# MC21R01_Inverter_2.net
KiCad netlist of a schematic drawn in Altium Designer
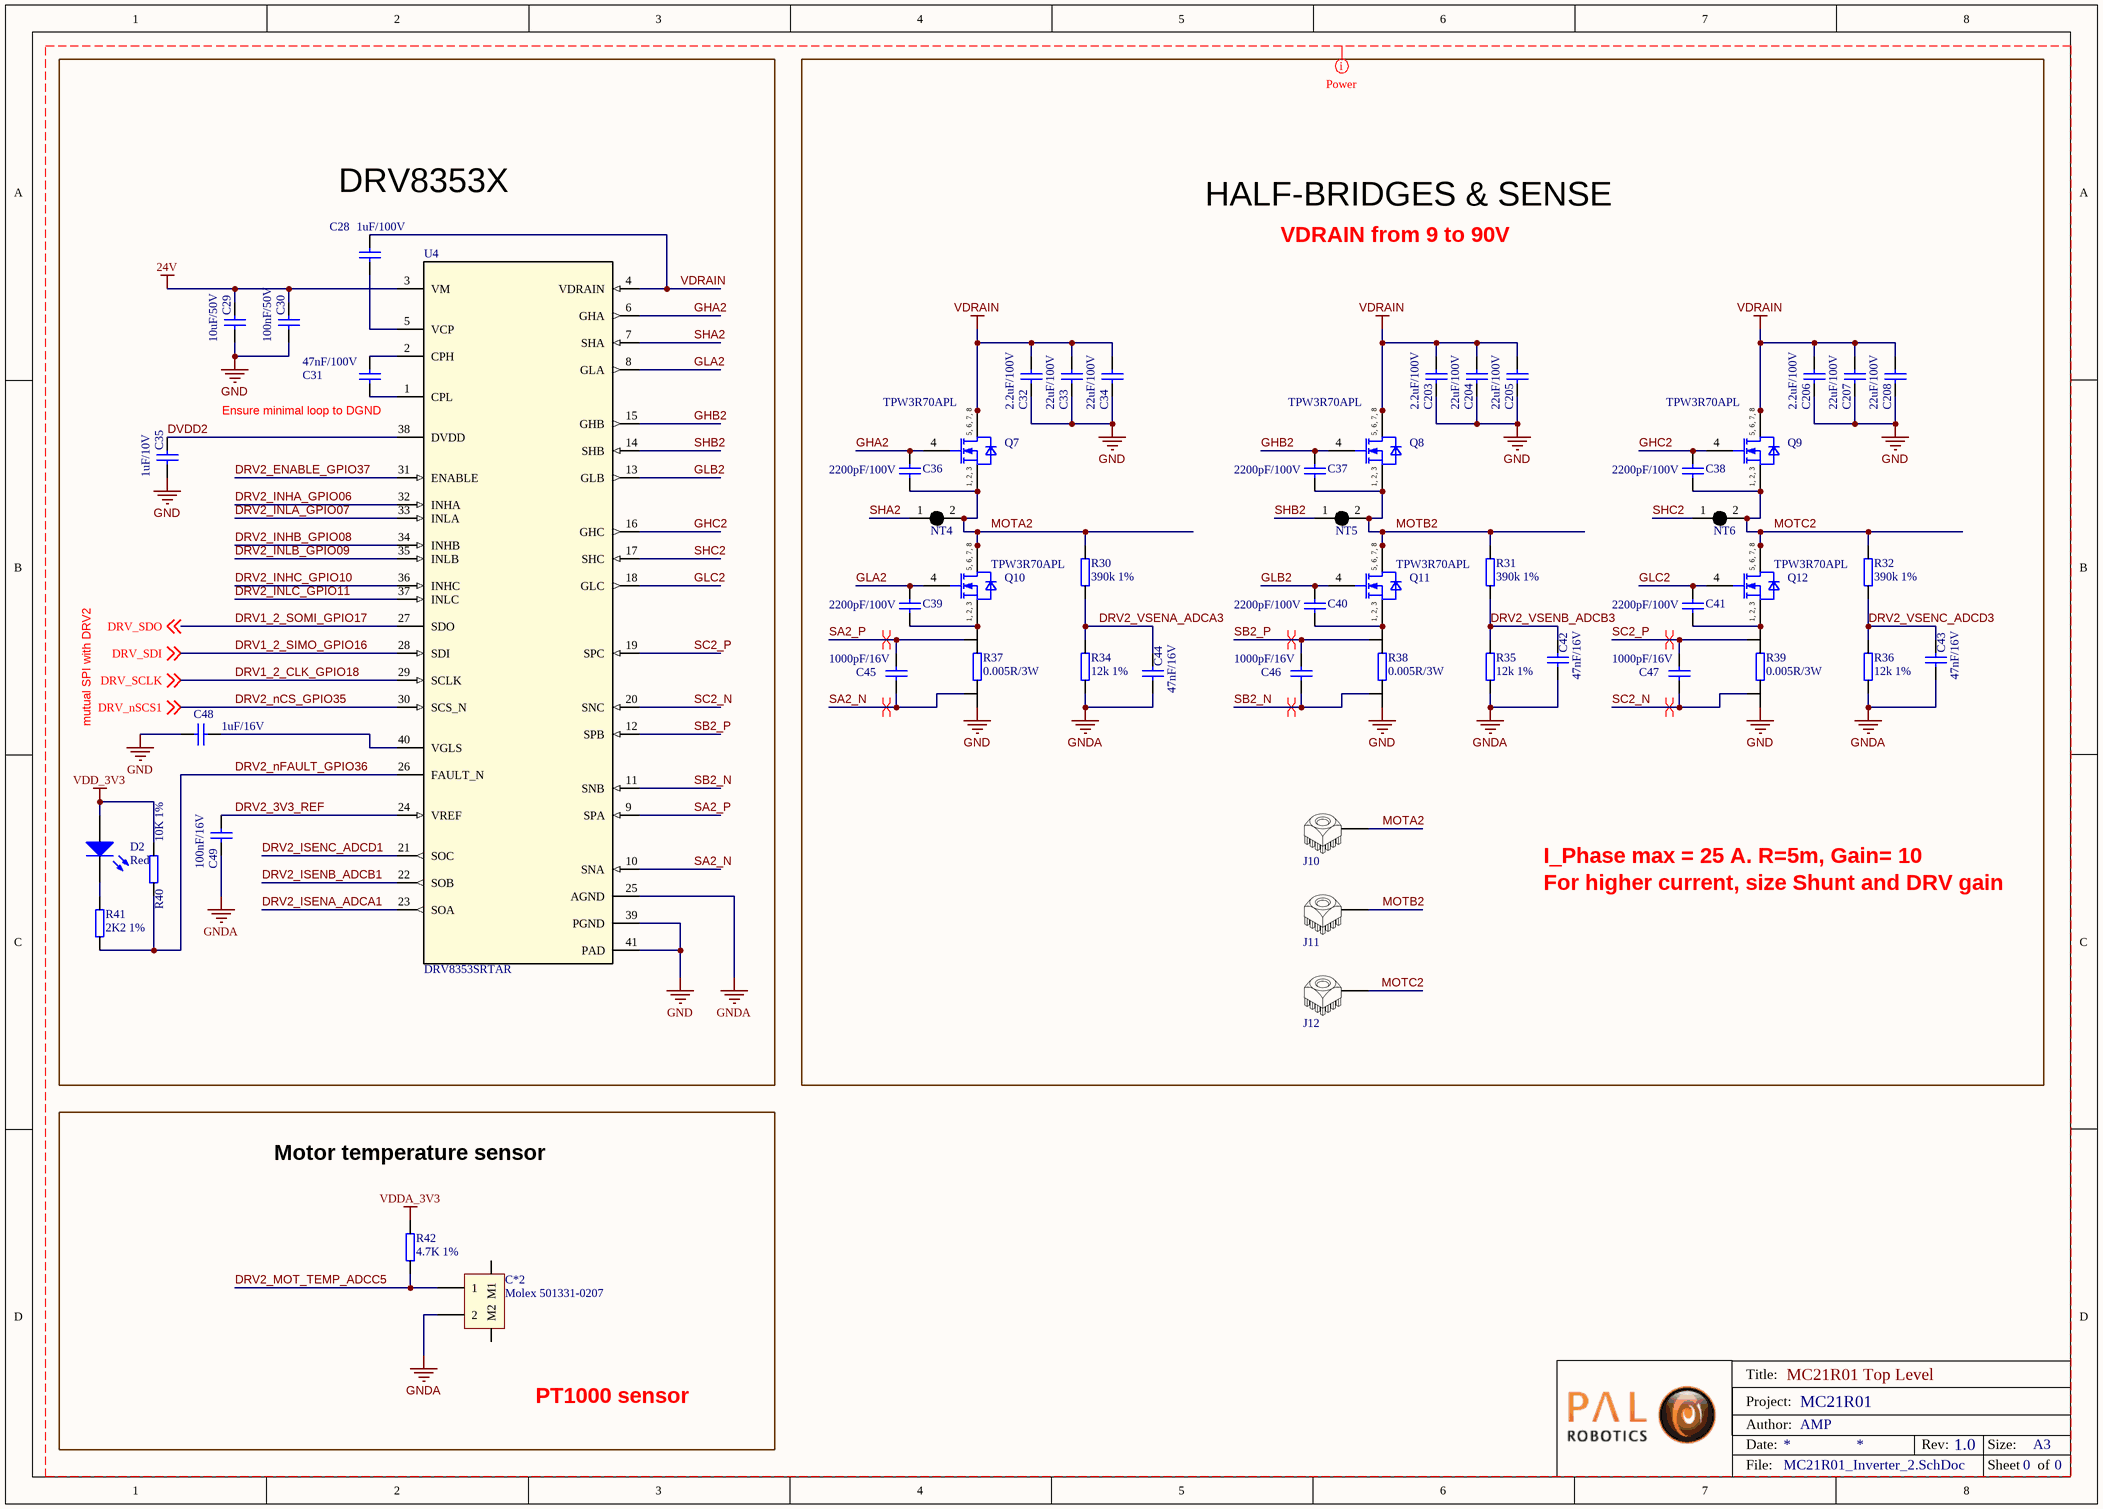
[diagram p0: MC21R01_Inverter_2.SchDoc]

(export (version "E")
  (design (tool "Eeschema 10.0.6"))
  (components
    (comp (ref "C*2")
      (value "Molex 501331-0207")
      (footprint "Molex 501331-0207")
      (description "PicoClasp 02 pin vertical")
      (libsource (lib "PAL_Molex") (part "Molex 501331-0207"))
    )
    (comp (ref "C28")
      (value "1uF/100V")
      (footprint "PAL_Capacitors:0805 SMD capacitor")
      (description "1 uF 100 V 0805  ±10% Tolerance X7R Multilayer Ceramic Chip Capacitor")
      (fields (field (name "Comment") "1uF/100V 0805 10% X7R"))
      (libsource (lib "PAL_Capacitors") (part "1uF/100V 0805 10% X7R"))
    )
    (comp (ref "C29")
      (value "10uF/50V")
      (footprint "PAL_Capacitors:1206 SMD Capacitor")
      (description "10 uF 50 V 1206 ±20% Tolerance X5R Multilayer Ceramic Chip Capacitor")
      (fields (field (name "Comment") "10uf/50V 1206 20% X5R"))
      (libsource (lib "PAL_Capacitors") (part "10uF/50V 1206 20% X5R"))
    )
    (comp (ref "C30")
      (value "100nF/50V")
      (footprint "PAL_Capacitors:0603 SMD capacitor")
      (description "100 nF 50 V 0603  ±10% Tolerance X7R Multilayer Ceramic Chip Capacitor")
      (fields (field (name "Comment") "100nF/50V 0603 10% X7R"))
      (libsource (lib "PAL_Capacitors") (part "100nF/50V 0603 10% X7R"))
    )
    (comp (ref "C31")
      (value "47nF/100V")
      (footprint "PAL_Capacitors:0603 SMD capacitor")
      (description "47 nF 100 V 0603 ±10% Tolerance X7R Multilayer Ceramic Chip Capacitor")
      (fields (field (name "Comment") "47nF/100V 0603 10% X7R"))
      (libsource (lib "PAL_Capacitors") (part "47nF/100V 0603 10% X7R_1"))
    )
    (comp (ref "C32")
      (value "2.2uF/100V")
      (footprint "1210 SMD capacitor h=2mm")
      (description "2.2 uF 100 V 1210  ±10% Tolerance X7R Multilayer Ceramic Chip Capacitor")
      (fields (field (name "Comment") "2.2uF/100V 1210 10% X7R"))
      (libsource (lib "PAL_Capacitors") (part "2.2uF/100V 1210 10% X7R"))
    )
    (comp (ref "C33")
      (value "22uF/100V")
      (footprint "PAL_Capacitors:2220 SMD Capacitor H=5MM")
      (description "22 uF 100 V 2220 ±20% Tolerance X7S Multilayer Ceramic Chip Capacitor")
      (fields (field (name "Comment") "22uF/100V 2220 20% X7S"))
      (libsource (lib "PAL_Capacitors") (part "22uF/100V 2220 20% X7S"))
    )
    (comp (ref "C34")
      (value "22uF/100V")
      (footprint "PAL_Capacitors:2220 SMD Capacitor H=5MM")
      (description "22 uF 100 V 2220 ±20% Tolerance X7S Multilayer Ceramic Chip Capacitor")
      (fields (field (name "Comment") "22uF/100V 2220 20% X7S"))
      (libsource (lib "PAL_Capacitors") (part "22uF/100V 2220 20% X7S"))
    )
    (comp (ref "C35")
      (value "1uF/10V")
      (footprint "PAL_Capacitors:0603 SMD capacitor")
      (description "1uF/10V 0603 10% Tolerance X7R Multilayer Ceramic Chip Capacitor")
      (fields (field (name "Comment") "1uF/10V 0603 10% X7R"))
      (libsource (lib "PAL_Capacitors") (part "1uF/10V 0603 10% X7R"))
    )
    (comp (ref "C36")
      (value "2200pF/100V")
      (footprint "PAL_Capacitors:0402 SMD Capacitor")
      (description "2200pF/100V 0402 10% Tolerance X7S Multilayer Ceramic Chip Capacitor")
      (fields (field (name "Comment") "2200pF/100V 0402 10% X7S"))
      (libsource (lib "PAL_Capacitors") (part "2200pF/100V 0402 10% X7S"))
    )
    (comp (ref "C37")
      (value "2200pF/100V")
      (footprint "PAL_Capacitors:0402 SMD Capacitor")
      (description "2200pF/100V 0402 10% Tolerance X7S Multilayer Ceramic Chip Capacitor")
      (fields (field (name "Comment") "2200pF/100V 0402 10% X7S"))
      (libsource (lib "PAL_Capacitors") (part "2200pF/100V 0402 10% X7S"))
    )
    (comp (ref "C38")
      (value "2200pF/100V")
      (footprint "PAL_Capacitors:0402 SMD Capacitor")
      (description "2200pF/100V 0402 10% Tolerance X7S Multilayer Ceramic Chip Capacitor")
      (fields (field (name "Comment") "2200pF/100V 0402 10% X7S"))
      (libsource (lib "PAL_Capacitors") (part "2200pF/100V 0402 10% X7S"))
    )
    (comp (ref "C39")
      (value "2200pF/100V")
      (footprint "PAL_Capacitors:0402 SMD Capacitor")
      (description "2200pF/100V 0402 10% Tolerance X7S Multilayer Ceramic Chip Capacitor")
      (fields (field (name "Comment") "2200pF/100V 0402 10% X7S"))
      (libsource (lib "PAL_Capacitors") (part "2200pF/100V 0402 10% X7S"))
    )
    (comp (ref "C40")
      (value "2200pF/100V")
      (footprint "PAL_Capacitors:0402 SMD Capacitor")
      (description "2200pF/100V 0402 10% Tolerance X7S Multilayer Ceramic Chip Capacitor")
      (fields (field (name "Comment") "2200pF/100V 0402 10% X7S"))
      (libsource (lib "PAL_Capacitors") (part "2200pF/100V 0402 10% X7S"))
    )
    (comp (ref "C41")
      (value "2200pF/100V")
      (footprint "PAL_Capacitors:0402 SMD Capacitor")
      (description "2200pF/100V 0402 10% Tolerance X7S Multilayer Ceramic Chip Capacitor")
      (fields (field (name "Comment") "2200pF/100V 0402 10% X7S"))
      (libsource (lib "PAL_Capacitors") (part "2200pF/100V 0402 10% X7S"))
    )
    (comp (ref "C42")
      (value "47nF/16V")
      (footprint "PAL_Capacitors:0402 SMD Capacitor")
      (description "47nF/16V 0402 10% Tolerance X7R Multilayer Ceramic Chip Capacitor")
      (fields (field (name "Comment") "47nF/16V 0402 10% X7R"))
      (libsource (lib "PAL_Capacitors") (part "47nF/16V 0402 10% X7R"))
    )
    (comp (ref "C43")
      (value "47nF/16V")
      (footprint "PAL_Capacitors:0402 SMD Capacitor")
      (description "47nF/16V 0402 10% Tolerance X7R Multilayer Ceramic Chip Capacitor")
      (fields (field (name "Comment") "47nF/16V 0402 10% X7R"))
      (libsource (lib "PAL_Capacitors") (part "47nF/16V 0402 10% X7R"))
    )
    (comp (ref "C44")
      (value "47nF/16V")
      (footprint "PAL_Capacitors:0402 SMD Capacitor")
      (description "47nF/16V 0402 10% Tolerance X7R Multilayer Ceramic Chip Capacitor")
      (fields (field (name "Comment") "47nF/16V 0402 10% X7R"))
      (libsource (lib "PAL_Capacitors") (part "47nF/16V 0402 10% X7R"))
    )
    (comp (ref "C45")
      (value "1000pF/16V")
      (footprint "PAL_Capacitors:0402 SMD Capacitor")
      (description "1000pF/16V 0402 10% Tolerance X7R Multilayer Ceramic Chip Capacitor")
      (fields (field (name "Comment") "1000pF/16V 0402 10% X7R"))
      (libsource (lib "PAL_Capacitors") (part "1000pF/16V 0402 10% X7R_1"))
    )
    (comp (ref "C46")
      (value "1000pF/16V")
      (footprint "PAL_Capacitors:0402 SMD Capacitor")
      (description "1000pF/16V 0402 10% Tolerance X7R Multilayer Ceramic Chip Capacitor")
      (fields (field (name "Comment") "1000pF/16V 0402 10% X7R"))
      (libsource (lib "PAL_Capacitors") (part "1000pF/16V 0402 10% X7R_1"))
    )
    (comp (ref "C47")
      (value "1000pF/16V")
      (footprint "PAL_Capacitors:0402 SMD Capacitor")
      (description "1000pF/16V 0402 10% Tolerance X7R Multilayer Ceramic Chip Capacitor")
      (fields (field (name "Comment") "1000pF/16V 0402 10% X7R"))
      (libsource (lib "PAL_Capacitors") (part "1000pF/16V 0402 10% X7R_1"))
    )
    (comp (ref "C48")
      (value "1uF/16V")
      (footprint "PAL_Capacitors:0603 SMD capacitor")
      (description "1uF/16V 0603 10% Tolerance X7R Multilayer Ceramic Chip Capacitor")
      (fields (field (name "Comment") "1uF/16V 0603 10% X7R"))
      (libsource (lib "PAL_Capacitors") (part "1uF/16V 0603 10% X7R"))
    )
    (comp (ref "C49")
      (value "100nF/16V")
      (footprint "PAL_Capacitors:0402 SMD Capacitor")
      (description "100nF/16V 0402 10% Tolerance X7R Multilayer Ceramic Chip Capacitor")
      (fields (field (name "Comment") "100nF/16V 0402 10% X7R"))
      (libsource (lib "PAL_Capacitors") (part "100nF/16V 0402 10% X7R"))
    )
    (comp (ref "C203")
      (value "2.2uF/100V")
      (footprint "1210 SMD capacitor h=2mm")
      (description "2.2 uF 100 V 1210  ±10% Tolerance X7R Multilayer Ceramic Chip Capacitor")
      (fields (field (name "Comment") "2.2uF/100V 1210 10% X7R"))
      (libsource (lib "PAL_Capacitors") (part "2.2uF/100V 1210 10% X7R"))
    )
    (comp (ref "C204")
      (value "22uF/100V")
      (footprint "PAL_Capacitors:2220 SMD Capacitor H=5MM")
      (description "22 uF 100 V 2220 ±20% Tolerance X7S Multilayer Ceramic Chip Capacitor")
      (fields (field (name "Comment") "22uF/100V 2220 20% X7S"))
      (libsource (lib "PAL_Capacitors") (part "22uF/100V 2220 20% X7S"))
    )
    (comp (ref "C205")
      (value "22uF/100V")
      (footprint "PAL_Capacitors:2220 SMD Capacitor H=5MM")
      (description "22 uF 100 V 2220 ±20% Tolerance X7S Multilayer Ceramic Chip Capacitor")
      (fields (field (name "Comment") "22uF/100V 2220 20% X7S"))
      (libsource (lib "PAL_Capacitors") (part "22uF/100V 2220 20% X7S"))
    )
    (comp (ref "C206")
      (value "2.2uF/100V")
      (footprint "1210 SMD capacitor h=2mm")
      (description "2.2 uF 100 V 1210  ±10% Tolerance X7R Multilayer Ceramic Chip Capacitor")
      (fields (field (name "Comment") "2.2uF/100V 1210 10% X7R"))
      (libsource (lib "PAL_Capacitors") (part "2.2uF/100V 1210 10% X7R"))
    )
    (comp (ref "C207")
      (value "22uF/100V")
      (footprint "PAL_Capacitors:2220 SMD Capacitor H=5MM")
      (description "22 uF 100 V 2220 ±20% Tolerance X7S Multilayer Ceramic Chip Capacitor")
      (fields (field (name "Comment") "22uF/100V 2220 20% X7S"))
      (libsource (lib "PAL_Capacitors") (part "22uF/100V 2220 20% X7S"))
    )
    (comp (ref "C208")
      (value "22uF/100V")
      (footprint "PAL_Capacitors:2220 SMD Capacitor H=5MM")
      (description "22 uF 100 V 2220 ±20% Tolerance X7S Multilayer Ceramic Chip Capacitor")
      (fields (field (name "Comment") "22uF/100V 2220 20% X7S"))
      (libsource (lib "PAL_Capacitors") (part "22uF/100V 2220 20% X7S"))
    )
    (comp (ref "D2")
      (value "Red")
      (footprint "0402 SMD LED Red")
      (description "Low Profile Chip LED, Red")
      (fields (field (name "MANUFACTURER") "ROHM") (field (name "MANUFACTURER PART NUMBER") "SML-P11UTT86R"))
      (libsource (lib "PAL_devices") (part "LED_0402_Red"))
    )
    (comp (ref "J10")
      (value "WE_7461094")
      (footprint "WE_7461094")
      (description "REDCUBE PRESS-FIT with external thread and full plain pin-plate WPSHFU, 130A, M3 screw, 9pins")
      (fields
        (field (name "MANUFACTURER") "WURTH ELEKTRONIK")
        (field (name "MANUFACTURER PART NUMBER") "7461094")
        (field (name "CREATED BY") "Yaiza Montes")
      )
      (libsource (lib "PAL_Wurth_2020") (part "WE_7461094"))
    )
    (comp (ref "J11")
      (value "WE_7461094")
      (footprint "WE_7461094")
      (description "REDCUBE PRESS-FIT with external thread and full plain pin-plate WPSHFU, 130A, M3 screw, 9pins")
      (fields
        (field (name "MANUFACTURER") "WURTH ELEKTRONIK")
        (field (name "MANUFACTURER PART NUMBER") "7461094")
        (field (name "CREATED BY") "Yaiza Montes")
      )
      (libsource (lib "PAL_Wurth_2020") (part "WE_7461094"))
    )
    (comp (ref "J12")
      (value "WE_7461094")
      (footprint "WE_7461094")
      (description "REDCUBE PRESS-FIT with external thread and full plain pin-plate WPSHFU, 130A, M3 screw, 9pins")
      (fields
        (field (name "MANUFACTURER") "WURTH ELEKTRONIK")
        (field (name "MANUFACTURER PART NUMBER") "7461094")
        (field (name "CREATED BY") "Yaiza Montes")
      )
      (libsource (lib "PAL_Wurth_2020") (part "WE_7461094"))
    )
    (comp (ref "NT4")
      (value "Net Tie SMD")
      (footprint "PAL_devices:Net Tie SMD 0.4x0.8mm")
      (description "Net Tie starpoint")
      (libsource (lib "PAL_devices") (part "Net Tie SMD"))
    )
    (comp (ref "NT5")
      (value "Net Tie SMD")
      (footprint "PAL_devices:Net Tie SMD 0.4x0.8mm")
      (description "Net Tie starpoint")
      (libsource (lib "PAL_devices") (part "Net Tie SMD"))
    )
    (comp (ref "NT6")
      (value "Net Tie SMD")
      (footprint "PAL_devices:Net Tie SMD 0.4x0.8mm")
      (description "Net Tie starpoint")
      (libsource (lib "PAL_devices") (part "Net Tie SMD"))
    )
    (comp (ref "Q7")
      (value "TPW3R70APL")
      (footprint "DSOP Advance Toshiba")
      (description "Silicon N-channel MOS (U-MOS-H)")
      (fields (field (name "MANUFACTURER") "Toshiba Semicon"))
      (libsource (lib "PAL_devices") (part "TPW3R70APL"))
    )
    (comp (ref "Q8")
      (value "TPW3R70APL")
      (footprint "DSOP Advance Toshiba")
      (description "Silicon N-channel MOS (U-MOS-H)")
      (fields (field (name "MANUFACTURER") "Toshiba Semicon"))
      (libsource (lib "PAL_devices") (part "TPW3R70APL"))
    )
    (comp (ref "Q9")
      (value "TPW3R70APL")
      (footprint "DSOP Advance Toshiba")
      (description "Silicon N-channel MOS (U-MOS-H)")
      (fields (field (name "MANUFACTURER") "Toshiba Semicon"))
      (libsource (lib "PAL_devices") (part "TPW3R70APL"))
    )
    (comp (ref "Q10")
      (value "TPW3R70APL")
      (footprint "DSOP Advance Toshiba")
      (description "Silicon N-channel MOS (U-MOS-H)")
      (fields (field (name "MANUFACTURER") "Toshiba Semicon"))
      (libsource (lib "PAL_devices") (part "TPW3R70APL"))
    )
    (comp (ref "Q11")
      (value "TPW3R70APL")
      (footprint "DSOP Advance Toshiba")
      (description "Silicon N-channel MOS (U-MOS-H)")
      (fields (field (name "MANUFACTURER") "Toshiba Semicon"))
      (libsource (lib "PAL_devices") (part "TPW3R70APL"))
    )
    (comp (ref "Q12")
      (value "TPW3R70APL")
      (footprint "DSOP Advance Toshiba")
      (description "Silicon N-channel MOS (U-MOS-H)")
      (fields (field (name "MANUFACTURER") "Toshiba Semicon"))
      (libsource (lib "PAL_devices") (part "TPW3R70APL"))
    )
    (comp (ref "R30")
      (value "390k 1%")
      (footprint "PAL_Resistors:0603 SMD resistor")
      (description "390k/150V 1% 0603 250mW SMD Resistor")
      (libsource (lib "PAL_Resistors") (part "390k/150V 1% 0603 250mW"))
    )
    (comp (ref "R31")
      (value "390k 1%")
      (footprint "PAL_Resistors:0603 SMD resistor")
      (description "390k/150V 1% 0603 250mW SMD Resistor")
      (libsource (lib "PAL_Resistors") (part "390k/150V 1% 0603 250mW"))
    )
    (comp (ref "R32")
      (value "390k 1%")
      (footprint "PAL_Resistors:0603 SMD resistor")
      (description "390k/150V 1% 0603 250mW SMD Resistor")
      (libsource (lib "PAL_Resistors") (part "390k/150V 1% 0603 250mW"))
    )
    (comp (ref "R34")
      (value "12k 1%")
      (footprint "PAL_Resistors:0603 SMD resistor")
      (description "12k/150V 1% 0603 250mW SMD Resistor")
      (libsource (lib "PAL_Resistors") (part "12k/150V 1% 0603 250mW"))
    )
    (comp (ref "R35")
      (value "12k 1%")
      (footprint "PAL_Resistors:0603 SMD resistor")
      (description "12k/150V 1% 0603 250mW SMD Resistor")
      (libsource (lib "PAL_Resistors") (part "12k/150V 1% 0603 250mW"))
    )
    (comp (ref "R36")
      (value "12k 1%")
      (footprint "PAL_Resistors:0603 SMD resistor")
      (description "12k/150V 1% 0603 250mW SMD Resistor")
      (libsource (lib "PAL_Resistors") (part "12k/150V 1% 0603 250mW"))
    )
    (comp (ref "R37")
      (value "0.005R/3W")
      (footprint "PAL_Resistors:2512 SMD Resistor V2 NETTIE")
      (description "0.005R/3W 1% 2512 shunt SMD Resistor")
      (libsource (lib "PAL_Resistors") (part "0.005R/3W 1% 2512 Shunt"))
    )
    (comp (ref "R38")
      (value "0.005R/3W")
      (footprint "PAL_Resistors:2512 SMD Resistor V2 NETTIE")
      (description "0.005R/3W 1% 2512 shunt SMD Resistor")
      (libsource (lib "PAL_Resistors") (part "0.005R/3W 1% 2512 Shunt"))
    )
    (comp (ref "R39")
      (value "0.005R/3W")
      (footprint "PAL_Resistors:2512 SMD Resistor V2 NETTIE")
      (description "0.005R/3W 1% 2512 shunt SMD Resistor")
      (libsource (lib "PAL_Resistors") (part "0.005R/3W 1% 2512 Shunt"))
    )
    (comp (ref "R40")
      (value "10K 1%")
      (footprint "0402 SMD rESISTOR")
      (description "10K/50V 1% 0402 100mW SMD Resistor")
      (libsource (lib "PAL_Resistors") (part "10K/50V 1% 0402 100mW"))
    )
    (comp (ref "R41")
      (value "2K2 1%")
      (footprint "0402 SMD rESISTOR")
      (description "2K2/50V 1% 0402 100mW SMD Resistor")
      (libsource (lib "PAL_Resistors") (part "2K2/50V 1% 0402 100mW"))
    )
    (comp (ref "R42")
      (value "4.7K 1%")
      (footprint "0402 SMD rESISTOR")
      (description "4.7K/50V 1% 0402 100mW SMD Resistor")
      (libsource (lib "PAL_Resistors") (part "4.7K/50V 1% 0402 100mW"))
    )
    (comp (ref "U4")
      (value "DRV8353SRTAR")
      (footprint "PAL_IPC-7351B_Footprints:QFN50P600X600X80_HS-41N")
      (description "102-V max 3-phase smart gate driver with current shunt amplifiers")
      (fields (field (name "MANUFACTURER") "Texas Instruments"))
      (libsource (lib "PAL_devices") (part "DRV8353SRTAR"))
    )
  )
  (nets
    (net (code "1") (name "/DRV2_3V3_REF") (class "Default")
      (node (ref "C49") (pin "1") (pinfunction "1_1") (pintype "passive"))
      (node (ref "U4") (pin "24") (pinfunction "VREF_24") (pintype "input"))
    )
    (net (code "2") (name "/DRV2_ENABLE_GPIO37") (class "Default")
      (node (ref "U4") (pin "31") (pinfunction "ENABLE_31") (pintype "input"))
    )
    (net (code "3") (name "/DRV2_INHA_GPIO06") (class "Default")
      (node (ref "U4") (pin "32") (pinfunction "INHA_32") (pintype "input"))
    )
    (net (code "4") (name "/DRV2_INHB_GPIO08") (class "Default")
      (node (ref "U4") (pin "34") (pinfunction "INHB_34") (pintype "input"))
    )
    (net (code "5") (name "/DRV2_INHC_GPIO10") (class "Default")
      (node (ref "U4") (pin "36") (pinfunction "INHC_36") (pintype "input"))
    )
    (net (code "6") (name "/DRV2_INLA_GPIO07") (class "Default")
      (node (ref "U4") (pin "33") (pinfunction "INLA_33") (pintype "input"))
    )
    (net (code "7") (name "/DRV2_INLB_GPIO09") (class "Default")
      (node (ref "U4") (pin "35") (pinfunction "INLB_35") (pintype "input"))
    )
    (net (code "8") (name "/DRV2_INLC_GPIO11") (class "Default")
      (node (ref "U4") (pin "37") (pinfunction "INLC_37") (pintype "input"))
    )
    (net (code "9") (name "/DRV2_ISENA_ADCA1") (class "Default")
      (node (ref "U4") (pin "23") (pinfunction "SOA_23") (pintype "output"))
    )
    (net (code "10") (name "/DRV2_ISENB_ADCB1") (class "Default")
      (node (ref "U4") (pin "22") (pinfunction "SOB_22") (pintype "output"))
    )
    (net (code "11") (name "/DRV2_ISENC_ADCD1") (class "Default")
      (node (ref "U4") (pin "21") (pinfunction "SOC_21") (pintype "output"))
    )
    (net (code "12") (name "/DRV2_MOT_TEMP_ADCC5") (class "Default")
      (node (ref "C*2") (pin "1") (pinfunction "1_1") (pintype "passive"))
      (node (ref "R42") (pin "1") (pinfunction "1_1") (pintype "passive"))
    )
    (net (code "13") (name "/DRV2_VSENA_ADCA3") (class "Default")
      (node (ref "C44") (pin "1") (pinfunction "1_1") (pintype "passive"))
      (node (ref "R30") (pin "1") (pinfunction "1_1") (pintype "passive"))
      (node (ref "R34") (pin "2") (pinfunction "2_2") (pintype "passive"))
    )
    (net (code "14") (name "/DRV2_VSENB_ADCB3") (class "Default")
      (node (ref "C42") (pin "1") (pinfunction "1_1") (pintype "passive"))
      (node (ref "R31") (pin "1") (pinfunction "1_1") (pintype "passive"))
      (node (ref "R35") (pin "2") (pinfunction "2_2") (pintype "passive"))
    )
    (net (code "15") (name "/DRV2_VSENC_ADCD3") (class "Default")
      (node (ref "C43") (pin "1") (pinfunction "1_1") (pintype "passive"))
      (node (ref "R32") (pin "1") (pinfunction "1_1") (pintype "passive"))
      (node (ref "R36") (pin "2") (pinfunction "2_2") (pintype "passive"))
    )
    (net (code "16") (name "/DRV2_nFAULT_GPIO36") (class "Default")
      (node (ref "R40") (pin "1") (pinfunction "1_1") (pintype "passive"))
      (node (ref "R41") (pin "1") (pinfunction "1_1") (pintype "passive"))
      (node (ref "U4") (pin "26") (pinfunction "FAULT_N_26") (pintype "open_collector"))
    )
    (net (code "17") (name "/DVDD2") (class "Default")
      (node (ref "C35") (pin "1") (pinfunction "1_1") (pintype "passive"))
      (node (ref "U4") (pin "38") (pinfunction "DVDD_38") (pintype "power_in"))
    )
    (net (code "18") (name "/GHA2") (class "Default")
      (node (ref "C36") (pin "1") (pinfunction "1_1") (pintype "passive"))
      (node (ref "Q7") (pin "4") (pinfunction "GATE_4") (pintype "passive"))
      (node (ref "U4") (pin "6") (pinfunction "GHA_6") (pintype "output"))
    )
    (net (code "19") (name "/GHB2") (class "Default")
      (node (ref "C37") (pin "1") (pinfunction "1_1") (pintype "passive"))
      (node (ref "Q8") (pin "4") (pinfunction "GATE_4") (pintype "passive"))
      (node (ref "U4") (pin "15") (pinfunction "GHB_15") (pintype "output"))
    )
    (net (code "20") (name "/GHC2") (class "Default")
      (node (ref "C38") (pin "1") (pinfunction "1_1") (pintype "passive"))
      (node (ref "Q9") (pin "4") (pinfunction "GATE_4") (pintype "passive"))
      (node (ref "U4") (pin "16") (pinfunction "GHC_16") (pintype "output"))
    )
    (net (code "21") (name "/GLA2") (class "Default")
      (node (ref "C39") (pin "1") (pinfunction "1_1") (pintype "passive"))
      (node (ref "Q10") (pin "4") (pinfunction "GATE_4") (pintype "passive"))
      (node (ref "U4") (pin "8") (pinfunction "GLA_8") (pintype "output"))
    )
    (net (code "22") (name "/GLB2") (class "Default")
      (node (ref "C40") (pin "1") (pinfunction "1_1") (pintype "passive"))
      (node (ref "Q11") (pin "4") (pinfunction "GATE_4") (pintype "passive"))
      (node (ref "U4") (pin "13") (pinfunction "GLB_13") (pintype "output"))
    )
    (net (code "23") (name "/GLC2") (class "Default")
      (node (ref "C41") (pin "1") (pinfunction "1_1") (pintype "passive"))
      (node (ref "Q12") (pin "4") (pinfunction "GATE_4") (pintype "passive"))
      (node (ref "U4") (pin "18") (pinfunction "GLC_18") (pintype "output"))
    )
    (net (code "24") (name "/MOTA2") (class "Default")
      (node (ref "C36") (pin "2") (pinfunction "2_2") (pintype "passive"))
      (node (ref "J10") (pin "1") (pinfunction "1_1") (pintype "passive"))
      (node (ref "NT4") (pin "2") (pinfunction "2_2") (pintype "passive"))
      (node (ref "Q10") (pin "5") (pinfunction "DRAIN_5") (pintype "passive"))
      (node (ref "Q10") (pin "6") (pinfunction "DRAIN_6") (pintype "passive"))
      (node (ref "Q10") (pin "7") (pinfunction "DRAIN_7") (pintype "passive"))
      (node (ref "Q10") (pin "8") (pinfunction "DRAIN_8") (pintype "passive"))
      (node (ref "Q7") (pin "1") (pinfunction "SOURCE_1") (pintype "passive"))
      (node (ref "Q7") (pin "2") (pinfunction "SOURCE_2") (pintype "passive"))
      (node (ref "Q7") (pin "3") (pinfunction "SOURCE_3") (pintype "passive"))
      (node (ref "R30") (pin "2") (pinfunction "2_2") (pintype "passive"))
    )
    (net (code "25") (name "/MOTB2") (class "Default")
      (node (ref "C37") (pin "2") (pinfunction "2_2") (pintype "passive"))
      (node (ref "J11") (pin "1") (pinfunction "1_1") (pintype "passive"))
      (node (ref "NT5") (pin "2") (pinfunction "2_2") (pintype "passive"))
      (node (ref "Q11") (pin "5") (pinfunction "DRAIN_5") (pintype "passive"))
      (node (ref "Q11") (pin "6") (pinfunction "DRAIN_6") (pintype "passive"))
      (node (ref "Q11") (pin "7") (pinfunction "DRAIN_7") (pintype "passive"))
      (node (ref "Q11") (pin "8") (pinfunction "DRAIN_8") (pintype "passive"))
      (node (ref "Q8") (pin "1") (pinfunction "SOURCE_1") (pintype "passive"))
      (node (ref "Q8") (pin "2") (pinfunction "SOURCE_2") (pintype "passive"))
      (node (ref "Q8") (pin "3") (pinfunction "SOURCE_3") (pintype "passive"))
      (node (ref "R31") (pin "2") (pinfunction "2_2") (pintype "passive"))
    )
    (net (code "26") (name "/MOTC2") (class "Default")
      (node (ref "C38") (pin "2") (pinfunction "2_2") (pintype "passive"))
      (node (ref "J12") (pin "1") (pinfunction "1_1") (pintype "passive"))
      (node (ref "NT6") (pin "2") (pinfunction "2_2") (pintype "passive"))
      (node (ref "Q12") (pin "5") (pinfunction "DRAIN_5") (pintype "passive"))
      (node (ref "Q12") (pin "6") (pinfunction "DRAIN_6") (pintype "passive"))
      (node (ref "Q12") (pin "7") (pinfunction "DRAIN_7") (pintype "passive"))
      (node (ref "Q12") (pin "8") (pinfunction "DRAIN_8") (pintype "passive"))
      (node (ref "Q9") (pin "1") (pinfunction "SOURCE_1") (pintype "passive"))
      (node (ref "Q9") (pin "2") (pinfunction "SOURCE_2") (pintype "passive"))
      (node (ref "Q9") (pin "3") (pinfunction "SOURCE_3") (pintype "passive"))
      (node (ref "R32") (pin "2") (pinfunction "2_2") (pintype "passive"))
    )
    (net (code "27") (name "/SA2_N") (class "Default")
      (node (ref "C45") (pin "2") (pinfunction "2_2") (pintype "passive"))
      (node (ref "R37") (pin "3") (pinfunction "3_3") (pintype "passive"))
      (node (ref "U4") (pin "10") (pinfunction "SNA_10") (pintype "input"))
    )
    (net (code "28") (name "/SA2_P") (class "Default")
      (node (ref "C45") (pin "1") (pinfunction "1_1") (pintype "passive"))
      (node (ref "R37") (pin "4") (pinfunction "4_4") (pintype "passive"))
      (node (ref "U4") (pin "9") (pinfunction "SPA_9") (pintype "input"))
    )
    (net (code "29") (name "/SB2_N") (class "Default")
      (node (ref "C46") (pin "2") (pinfunction "2_2") (pintype "passive"))
      (node (ref "R38") (pin "3") (pinfunction "3_3") (pintype "passive"))
      (node (ref "U4") (pin "11") (pinfunction "SNB_11") (pintype "input"))
    )
    (net (code "30") (name "/SB2_P") (class "Default")
      (node (ref "C46") (pin "1") (pinfunction "1_1") (pintype "passive"))
      (node (ref "R38") (pin "4") (pinfunction "4_4") (pintype "passive"))
      (node (ref "U4") (pin "12") (pinfunction "SPB_12") (pintype "input"))
    )
    (net (code "31") (name "/SC2_N") (class "Default")
      (node (ref "C47") (pin "2") (pinfunction "2_2") (pintype "passive"))
      (node (ref "R39") (pin "3") (pinfunction "3_3") (pintype "passive"))
      (node (ref "U4") (pin "20") (pinfunction "SNC_20") (pintype "input"))
    )
    (net (code "32") (name "/SC2_P") (class "Default")
      (node (ref "C47") (pin "1") (pinfunction "1_1") (pintype "passive"))
      (node (ref "R39") (pin "4") (pinfunction "4_4") (pintype "passive"))
      (node (ref "U4") (pin "19") (pinfunction "SPC_19") (pintype "input"))
    )
    (net (code "33") (name "/SHA2") (class "Default")
      (node (ref "NT4") (pin "1") (pinfunction "1_1") (pintype "passive"))
      (node (ref "U4") (pin "7") (pinfunction "SHA_7") (pintype "input"))
    )
    (net (code "34") (name "/SHB2") (class "Default")
      (node (ref "NT5") (pin "1") (pinfunction "1_1") (pintype "passive"))
      (node (ref "U4") (pin "14") (pinfunction "SHB_14") (pintype "input"))
    )
    (net (code "35") (name "/SHC2") (class "Default")
      (node (ref "NT6") (pin "1") (pinfunction "1_1") (pintype "passive"))
      (node (ref "U4") (pin "17") (pinfunction "SHC_17") (pintype "input"))
    )
    (net (code "36") (name "24V") (class "Default")
      (node (ref "C29") (pin "1") (pinfunction "1_1") (pintype "passive"))
      (node (ref "C30") (pin "1") (pinfunction "1_1") (pintype "passive"))
      (node (ref "U4") (pin "3") (pinfunction "VM_3") (pintype "power_in"))
    )
    (net (code "37") (name "DRV_SCLK") (class "Default")
      (node (ref "U4") (pin "29") (pinfunction "SCLK_29") (pintype "input"))
    )
    (net (code "38") (name "DRV_SDI") (class "Default")
      (node (ref "U4") (pin "28") (pinfunction "SDI_28") (pintype "input"))
    )
    (net (code "39") (name "DRV_SDO") (class "Default")
      (node (ref "U4") (pin "27") (pinfunction "SDO_27") (pintype "passive"))
    )
    (net (code "40") (name "DRV_nSCS1") (class "Default")
      (node (ref "U4") (pin "30") (pinfunction "SCS_N_30") (pintype "input"))
    )
    (net (code "41") (name "GND") (class "Default")
      (node (ref "C203") (pin "2") (pinfunction "2_2") (pintype "passive"))
      (node (ref "C204") (pin "2") (pinfunction "2_2") (pintype "passive"))
      (node (ref "C205") (pin "2") (pinfunction "2_2") (pintype "passive"))
      (node (ref "C206") (pin "2") (pinfunction "2_2") (pintype "passive"))
      (node (ref "C207") (pin "2") (pinfunction "2_2") (pintype "passive"))
      (node (ref "C208") (pin "2") (pinfunction "2_2") (pintype "passive"))
      (node (ref "C29") (pin "2") (pinfunction "2_2") (pintype "passive"))
      (node (ref "C30") (pin "2") (pinfunction "2_2") (pintype "passive"))
      (node (ref "C32") (pin "2") (pinfunction "2_2") (pintype "passive"))
      (node (ref "C33") (pin "2") (pinfunction "2_2") (pintype "passive"))
      (node (ref "C34") (pin "2") (pinfunction "2_2") (pintype "passive"))
      (node (ref "C35") (pin "2") (pinfunction "2_2") (pintype "passive"))
      (node (ref "C48") (pin "1") (pinfunction "1_1") (pintype "passive"))
      (node (ref "R37") (pin "1") (pinfunction "1_1") (pintype "passive"))
      (node (ref "R38") (pin "1") (pinfunction "1_1") (pintype "passive"))
      (node (ref "R39") (pin "1") (pinfunction "1_1") (pintype "passive"))
      (node (ref "U4") (pin "39") (pinfunction "PGND_39") (pintype "power_in"))
      (node (ref "U4") (pin "41") (pinfunction "PAD_41") (pintype "power_in"))
    )
    (net (code "42") (name "GNDA") (class "Default")
      (node (ref "C*2") (pin "2") (pinfunction "2_2") (pintype "passive"))
      (node (ref "C42") (pin "2") (pinfunction "2_2") (pintype "passive"))
      (node (ref "C43") (pin "2") (pinfunction "2_2") (pintype "passive"))
      (node (ref "C44") (pin "2") (pinfunction "2_2") (pintype "passive"))
      (node (ref "C49") (pin "2") (pinfunction "2_2") (pintype "passive"))
      (node (ref "R34") (pin "1") (pinfunction "1_1") (pintype "passive"))
      (node (ref "R35") (pin "1") (pinfunction "1_1") (pintype "passive"))
      (node (ref "R36") (pin "1") (pinfunction "1_1") (pintype "passive"))
      (node (ref "U4") (pin "25") (pinfunction "AGND_25") (pintype "power_in"))
    )
    (net (code "43") (name "Net-(C39-Pad2)") (class "Default")
      (node (ref "C39") (pin "2") (pinfunction "2_2") (pintype "passive"))
      (node (ref "Q10") (pin "1") (pinfunction "SOURCE_1") (pintype "passive"))
      (node (ref "Q10") (pin "2") (pinfunction "SOURCE_2") (pintype "passive"))
      (node (ref "Q10") (pin "3") (pinfunction "SOURCE_3") (pintype "passive"))
      (node (ref "R37") (pin "2") (pinfunction "2_2") (pintype "passive"))
    )
    (net (code "44") (name "Net-(C40-Pad2)") (class "Default")
      (node (ref "C40") (pin "2") (pinfunction "2_2") (pintype "passive"))
      (node (ref "Q11") (pin "1") (pinfunction "SOURCE_1") (pintype "passive"))
      (node (ref "Q11") (pin "2") (pinfunction "SOURCE_2") (pintype "passive"))
      (node (ref "Q11") (pin "3") (pinfunction "SOURCE_3") (pintype "passive"))
      (node (ref "R38") (pin "2") (pinfunction "2_2") (pintype "passive"))
    )
    (net (code "45") (name "Net-(C41-Pad2)") (class "Default")
      (node (ref "C41") (pin "2") (pinfunction "2_2") (pintype "passive"))
      (node (ref "Q12") (pin "1") (pinfunction "SOURCE_1") (pintype "passive"))
      (node (ref "Q12") (pin "2") (pinfunction "SOURCE_2") (pintype "passive"))
      (node (ref "Q12") (pin "3") (pinfunction "SOURCE_3") (pintype "passive"))
      (node (ref "R39") (pin "2") (pinfunction "2_2") (pintype "passive"))
    )
    (net (code "46") (name "Net-(D2-PadK)") (class "Default")
      (node (ref "D2") (pin "K") (pinfunction "K_K") (pintype "passive"))
      (node (ref "R41") (pin "2") (pinfunction "2_2") (pintype "passive"))
    )
    (net (code "47") (name "Net-(U4-CPH)") (class "Default")
      (node (ref "C31") (pin "1") (pinfunction "1_1") (pintype "passive"))
      (node (ref "U4") (pin "2") (pinfunction "CPH_2") (pintype "passive"))
    )
    (net (code "48") (name "Net-(U4-CPL)") (class "Default")
      (node (ref "C31") (pin "2") (pinfunction "2_2") (pintype "passive"))
      (node (ref "U4") (pin "1") (pinfunction "CPL_1") (pintype "passive"))
    )
    (net (code "49") (name "Net-(U4-VCP)") (class "Default")
      (node (ref "C28") (pin "2") (pinfunction "2_2") (pintype "passive"))
      (node (ref "U4") (pin "5") (pinfunction "VCP_5") (pintype "power_in"))
    )
    (net (code "50") (name "Net-(U4-VGLS)") (class "Default")
      (node (ref "C48") (pin "2") (pinfunction "2_2") (pintype "passive"))
      (node (ref "U4") (pin "40") (pinfunction "VGLS_40") (pintype "power_in"))
    )
    (net (code "51") (name "VDDA_3V3") (class "Default")
      (node (ref "R42") (pin "2") (pinfunction "2_2") (pintype "passive"))
    )
    (net (code "52") (name "VDD_3V3") (class "Default")
      (node (ref "D2") (pin "A") (pinfunction "A_A") (pintype "passive"))
      (node (ref "R40") (pin "2") (pinfunction "2_2") (pintype "passive"))
    )
    (net (code "53") (name "VDRAIN") (class "Default")
      (node (ref "C203") (pin "1") (pinfunction "1_1") (pintype "passive"))
      (node (ref "C204") (pin "1") (pinfunction "1_1") (pintype "passive"))
      (node (ref "C205") (pin "1") (pinfunction "1_1") (pintype "passive"))
      (node (ref "C206") (pin "1") (pinfunction "1_1") (pintype "passive"))
      (node (ref "C207") (pin "1") (pinfunction "1_1") (pintype "passive"))
      (node (ref "C208") (pin "1") (pinfunction "1_1") (pintype "passive"))
      (node (ref "C28") (pin "1") (pinfunction "1_1") (pintype "passive"))
      (node (ref "C32") (pin "1") (pinfunction "1_1") (pintype "passive"))
      (node (ref "C33") (pin "1") (pinfunction "1_1") (pintype "passive"))
      (node (ref "C34") (pin "1") (pinfunction "1_1") (pintype "passive"))
      (node (ref "Q7") (pin "5") (pinfunction "DRAIN_5") (pintype "passive"))
      (node (ref "Q7") (pin "6") (pinfunction "DRAIN_6") (pintype "passive"))
      (node (ref "Q7") (pin "7") (pinfunction "DRAIN_7") (pintype "passive"))
      (node (ref "Q7") (pin "8") (pinfunction "DRAIN_8") (pintype "passive"))
      (node (ref "Q8") (pin "5") (pinfunction "DRAIN_5") (pintype "passive"))
      (node (ref "Q8") (pin "6") (pinfunction "DRAIN_6") (pintype "passive"))
      (node (ref "Q8") (pin "7") (pinfunction "DRAIN_7") (pintype "passive"))
      (node (ref "Q8") (pin "8") (pinfunction "DRAIN_8") (pintype "passive"))
      (node (ref "Q9") (pin "5") (pinfunction "DRAIN_5") (pintype "passive"))
      (node (ref "Q9") (pin "6") (pinfunction "DRAIN_6") (pintype "passive"))
      (node (ref "Q9") (pin "7") (pinfunction "DRAIN_7") (pintype "passive"))
      (node (ref "Q9") (pin "8") (pinfunction "DRAIN_8") (pintype "passive"))
      (node (ref "U4") (pin "4") (pinfunction "VDRAIN_4") (pintype "input"))
    )
    (net (code "54") (name "unconnected-(C*2-PadM1)") (class "Default")
      (node (ref "C*2") (pin "M1") (pinfunction "M1_M1") (pintype "passive"))
    )
    (net (code "55") (name "unconnected-(C*2-PadM2)") (class "Default")
      (node (ref "C*2") (pin "M2") (pinfunction "M2_M2") (pintype "passive"))
    )
  )
)
